# MotorControllerV7_HBridge2.net
KiCad netlist of a schematic drawn in EAGLE
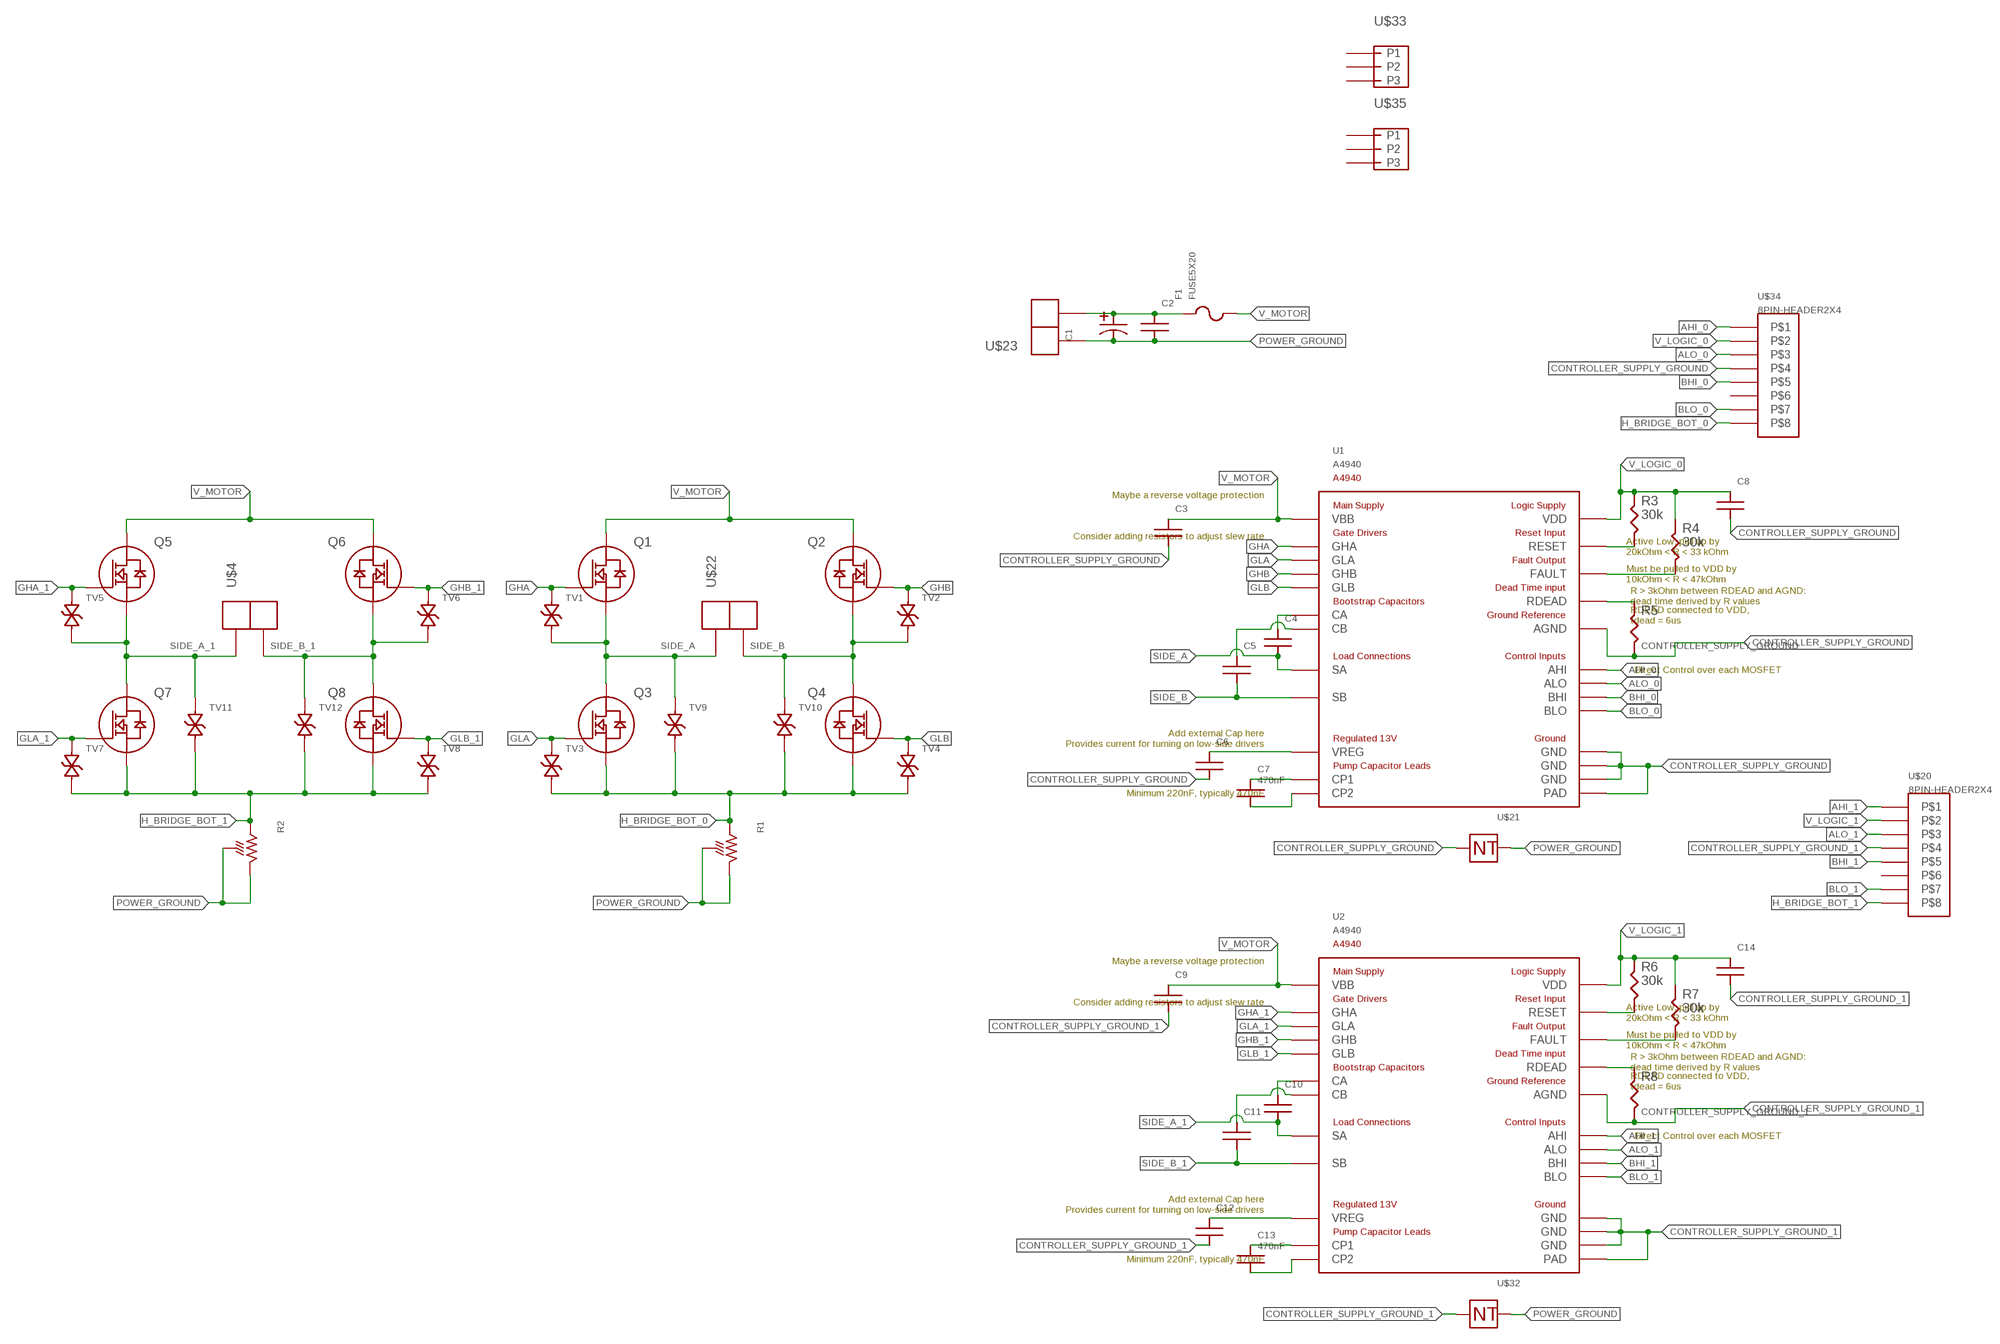
[diagram p0: schematic, sheet 1]

(export (version "E")
  (design (tool "Eeschema 10.0.6"))
  (components
    (comp (ref "C1")
      (value "CAPACITORESK_H4")
      (footprint "eagle-import:ESK_H4_CAPACITOR")
      (libsource (lib "eagle-import") (part "CAPACITORESK_H4"))
    )
    (comp (ref "C2")
      (value "CAPACITOR-UNPOLARIZED0805")
      (footprint "eagle-import:0805_STACKPOLERESISTOR")
      (libsource (lib "eagle-import") (part "CAPACITOR-UNPOLARIZED0805"))
    )
    (comp (ref "C3")
      (value "CAPACITOR-UNPOLARIZED0805")
      (footprint "eagle-import:0805_STACKPOLERESISTOR")
      (libsource (lib "eagle-import") (part "CAPACITOR-UNPOLARIZED0805"))
    )
    (comp (ref "C4")
      (value "CAPACITOR-UNPOLARIZED0805")
      (footprint "eagle-import:0805_STACKPOLERESISTOR")
      (libsource (lib "eagle-import") (part "CAPACITOR-UNPOLARIZED0805"))
    )
    (comp (ref "C5")
      (value "CAPACITOR-UNPOLARIZED0805")
      (footprint "eagle-import:0805_STACKPOLERESISTOR")
      (libsource (lib "eagle-import") (part "CAPACITOR-UNPOLARIZED0805"))
    )
    (comp (ref "C6")
      (value "CAPACITOR-UNPOLARIZED0805")
      (footprint "eagle-import:0805_STACKPOLERESISTOR")
      (libsource (lib "eagle-import") (part "CAPACITOR-UNPOLARIZED0805"))
    )
    (comp (ref "C7")
      (value "470nF")
      (footprint "eagle-import:0805_STACKPOLERESISTOR")
      (libsource (lib "eagle-import") (part "CAPACITOR-UNPOLARIZED0805"))
    )
    (comp (ref "C8")
      (value "CAPACITOR-UNPOLARIZED0805")
      (footprint "eagle-import:0805_STACKPOLERESISTOR")
      (libsource (lib "eagle-import") (part "CAPACITOR-UNPOLARIZED0805"))
    )
    (comp (ref "C9")
      (value "CAPACITOR-UNPOLARIZED0805")
      (footprint "eagle-import:0805_STACKPOLERESISTOR")
      (libsource (lib "eagle-import") (part "CAPACITOR-UNPOLARIZED0805"))
    )
    (comp (ref "C10")
      (value "CAPACITOR-UNPOLARIZED0805")
      (footprint "eagle-import:0805_STACKPOLERESISTOR")
      (libsource (lib "eagle-import") (part "CAPACITOR-UNPOLARIZED0805"))
    )
    (comp (ref "C11")
      (value "CAPACITOR-UNPOLARIZED0805")
      (footprint "eagle-import:0805_STACKPOLERESISTOR")
      (libsource (lib "eagle-import") (part "CAPACITOR-UNPOLARIZED0805"))
    )
    (comp (ref "C12")
      (value "CAPACITOR-UNPOLARIZED0805")
      (footprint "eagle-import:0805_STACKPOLERESISTOR")
      (libsource (lib "eagle-import") (part "CAPACITOR-UNPOLARIZED0805"))
    )
    (comp (ref "C13")
      (value "470nF")
      (footprint "eagle-import:0805_STACKPOLERESISTOR")
      (libsource (lib "eagle-import") (part "CAPACITOR-UNPOLARIZED0805"))
    )
    (comp (ref "C14")
      (value "CAPACITOR-UNPOLARIZED0805")
      (footprint "eagle-import:0805_STACKPOLERESISTOR")
      (libsource (lib "eagle-import") (part "CAPACITOR-UNPOLARIZED0805"))
    )
    (comp (ref "F1")
      (value "FUSE5X20")
      (footprint "eagle-import:LITTLEFUSE_5X20_HOLDER")
      (libsource (lib "eagle-import") (part "FUSE5X20"))
    )
    (comp (ref "Q1")
      (value "NMOSSOT669")
      (footprint "eagle-import:SOT669")
      (libsource (lib "eagle-import") (part "NMOSSOT669"))
    )
    (comp (ref "Q2")
      (value "NMOSSOT669")
      (footprint "eagle-import:SOT669")
      (libsource (lib "eagle-import") (part "NMOSSOT669"))
    )
    (comp (ref "Q3")
      (value "NMOSSOT669")
      (footprint "eagle-import:SOT669")
      (libsource (lib "eagle-import") (part "NMOSSOT669"))
    )
    (comp (ref "Q4")
      (value "NMOSSOT669")
      (footprint "eagle-import:SOT669")
      (libsource (lib "eagle-import") (part "NMOSSOT669"))
    )
    (comp (ref "Q5")
      (value "NMOSSOT669")
      (footprint "eagle-import:SOT669")
      (libsource (lib "eagle-import") (part "NMOSSOT669"))
    )
    (comp (ref "Q6")
      (value "NMOSSOT669")
      (footprint "eagle-import:SOT669")
      (libsource (lib "eagle-import") (part "NMOSSOT669"))
    )
    (comp (ref "Q7")
      (value "NMOSSOT669")
      (footprint "eagle-import:SOT669")
      (libsource (lib "eagle-import") (part "NMOSSOT669"))
    )
    (comp (ref "Q8")
      (value "NMOSSOT669")
      (footprint "eagle-import:SOT669")
      (libsource (lib "eagle-import") (part "NMOSSOT669"))
    )
    (comp (ref "R1")
      (value "RESISTOR_HEATSUNK")
      (footprint "eagle-import:TO-252")
      (libsource (lib "eagle-import") (part "RESISTOR_HEATSUNK"))
    )
    (comp (ref "R2")
      (value "RESISTOR_HEATSUNK")
      (footprint "eagle-import:TO-252")
      (libsource (lib "eagle-import") (part "RESISTOR_HEATSUNK"))
    )
    (comp (ref "R3")
      (value "30k")
      (footprint "eagle-import:0805_STACKPOLERESISTOR")
      (libsource (lib "eagle-import") (part "RESISTOR"))
    )
    (comp (ref "R4")
      (value "30k")
      (footprint "eagle-import:0805_STACKPOLERESISTOR")
      (libsource (lib "eagle-import") (part "RESISTOR"))
    )
    (comp (ref "R5")
      (value "RESISTOR")
      (footprint "eagle-import:0805_STACKPOLERESISTOR")
      (libsource (lib "eagle-import") (part "RESISTOR"))
    )
    (comp (ref "R6")
      (value "30k")
      (footprint "eagle-import:0805_STACKPOLERESISTOR")
      (libsource (lib "eagle-import") (part "RESISTOR"))
    )
    (comp (ref "R7")
      (value "30k")
      (footprint "eagle-import:0805_STACKPOLERESISTOR")
      (libsource (lib "eagle-import") (part "RESISTOR"))
    )
    (comp (ref "R8")
      (value "RESISTOR")
      (footprint "eagle-import:0805_STACKPOLERESISTOR")
      (libsource (lib "eagle-import") (part "RESISTOR"))
    )
    (comp (ref "TV1")
      (value "TVS_BIDIRECTIONALDO-214AC")
      (footprint "eagle-import:DO-214AC")
      (libsource (lib "eagle-import") (part "TVS_BIDIRECTIONALDO-214AC"))
    )
    (comp (ref "TV2")
      (value "TVS_BIDIRECTIONALDO-214AC")
      (footprint "eagle-import:DO-214AC")
      (libsource (lib "eagle-import") (part "TVS_BIDIRECTIONALDO-214AC"))
    )
    (comp (ref "TV3")
      (value "TVS_BIDIRECTIONALDO-214AC")
      (footprint "eagle-import:DO-214AC")
      (libsource (lib "eagle-import") (part "TVS_BIDIRECTIONALDO-214AC"))
    )
    (comp (ref "TV4")
      (value "TVS_BIDIRECTIONALDO-214AC")
      (footprint "eagle-import:DO-214AC")
      (libsource (lib "eagle-import") (part "TVS_BIDIRECTIONALDO-214AC"))
    )
    (comp (ref "TV5")
      (value "TVS_BIDIRECTIONALDO-214AC")
      (footprint "eagle-import:DO-214AC")
      (libsource (lib "eagle-import") (part "TVS_BIDIRECTIONALDO-214AC"))
    )
    (comp (ref "TV6")
      (value "TVS_BIDIRECTIONALDO-214AC")
      (footprint "eagle-import:DO-214AC")
      (libsource (lib "eagle-import") (part "TVS_BIDIRECTIONALDO-214AC"))
    )
    (comp (ref "TV7")
      (value "TVS_BIDIRECTIONALDO-214AC")
      (footprint "eagle-import:DO-214AC")
      (libsource (lib "eagle-import") (part "TVS_BIDIRECTIONALDO-214AC"))
    )
    (comp (ref "TV8")
      (value "TVS_BIDIRECTIONALDO-214AC")
      (footprint "eagle-import:DO-214AC")
      (libsource (lib "eagle-import") (part "TVS_BIDIRECTIONALDO-214AC"))
    )
    (comp (ref "TV9")
      (value "TVS_BIDIRECTIONAL")
      (footprint "eagle-import:SMB")
      (libsource (lib "eagle-import") (part "TVS_BIDIRECTIONAL"))
    )
    (comp (ref "TV10")
      (value "TVS_BIDIRECTIONAL")
      (footprint "eagle-import:SMB")
      (libsource (lib "eagle-import") (part "TVS_BIDIRECTIONAL"))
    )
    (comp (ref "TV11")
      (value "TVS_BIDIRECTIONAL")
      (footprint "eagle-import:SMB")
      (libsource (lib "eagle-import") (part "TVS_BIDIRECTIONAL"))
    )
    (comp (ref "TV12")
      (value "TVS_BIDIRECTIONAL")
      (footprint "eagle-import:SMB")
      (libsource (lib "eagle-import") (part "TVS_BIDIRECTIONAL"))
    )
    (comp (ref "U$4")
      (value "2PIN-HEADERANDERSON_RIGHTANGLE")
      (footprint "eagle-import:ANDERSON_RIGHTANGLE_X2")
      (libsource (lib "eagle-import") (part "2PIN-HEADERANDERSON_RIGHTANGLE"))
    )
    (comp (ref "U$20")
      (value "8PIN-HEADER2X4")
      (footprint "eagle-import:8PIN_2X4")
      (libsource (lib "eagle-import") (part "8PIN-HEADER2X4"))
    )
    (comp (ref "U$21")
      (value "NET_TIE1MM")
      (footprint "eagle-import:NET_TIE")
      (libsource (lib "eagle-import") (part "NET_TIE1MM"))
    )
    (comp (ref "U$22")
      (value "2PIN-HEADERANDERSON_RIGHTANGLE")
      (footprint "eagle-import:ANDERSON_RIGHTANGLE_X2")
      (libsource (lib "eagle-import") (part "2PIN-HEADERANDERSON_RIGHTANGLE"))
    )
    (comp (ref "U$23")
      (value "2PIN-HEADERANDERSON_RIGHTANGLE")
      (footprint "eagle-import:ANDERSON_RIGHTANGLE_X2")
      (libsource (lib "eagle-import") (part "2PIN-HEADERANDERSON_RIGHTANGLE"))
    )
    (comp (ref "U$32")
      (value "NET_TIE1MM")
      (footprint "eagle-import:NET_TIE")
      (libsource (lib "eagle-import") (part "NET_TIE1MM"))
    )
    (comp (ref "U$33")
      (value "3PIN_HEADER")
      (footprint "eagle-import:3PIN_HEADER")
      (libsource (lib "eagle-import") (part "3PIN_HEADER"))
    )
    (comp (ref "U$34")
      (value "8PIN-HEADER2X4")
      (footprint "eagle-import:8PIN_2X4")
      (libsource (lib "eagle-import") (part "8PIN-HEADER2X4"))
    )
    (comp (ref "U$35")
      (value "3PIN_HEADER")
      (footprint "eagle-import:3PIN_HEADER")
      (libsource (lib "eagle-import") (part "3PIN_HEADER"))
    )
    (comp (ref "U1")
      (value "A4940")
      (footprint "eagle-import:LP_24-PIN_TSSOP")
      (libsource (lib "eagle-import") (part "A4940"))
    )
    (comp (ref "U2")
      (value "A4940")
      (footprint "eagle-import:LP_24-PIN_TSSOP")
      (libsource (lib "eagle-import") (part "A4940"))
    )
  )
  (nets
    (net (code "1") (name "AHI_0") (class "Default")
      (node (ref "U$34") (pin "1") (pinfunction "P$1_1") (pintype "bidirectional"))
      (node (ref "U1") (pin "20") (pinfunction "AHI_20") (pintype "bidirectional"))
    )
    (net (code "2") (name "AHI_1") (class "Default")
      (node (ref "U$20") (pin "1") (pinfunction "P$1_1") (pintype "bidirectional"))
      (node (ref "U2") (pin "20") (pinfunction "AHI_20") (pintype "bidirectional"))
    )
    (net (code "3") (name "ALO_0") (class "Default")
      (node (ref "U$34") (pin "3") (pinfunction "P$3_3") (pintype "bidirectional"))
      (node (ref "U1") (pin "19") (pinfunction "ALO_19") (pintype "bidirectional"))
    )
    (net (code "4") (name "ALO_1") (class "Default")
      (node (ref "U$20") (pin "3") (pinfunction "P$3_3") (pintype "bidirectional"))
      (node (ref "U2") (pin "19") (pinfunction "ALO_19") (pintype "bidirectional"))
    )
    (net (code "5") (name "BHI_0") (class "Default")
      (node (ref "U$34") (pin "5") (pinfunction "P$5_5") (pintype "bidirectional"))
      (node (ref "U1") (pin "18") (pinfunction "BHI_18") (pintype "bidirectional"))
    )
    (net (code "6") (name "BHI_1") (class "Default")
      (node (ref "U$20") (pin "5") (pinfunction "P$5_5") (pintype "bidirectional"))
      (node (ref "U2") (pin "18") (pinfunction "BHI_18") (pintype "bidirectional"))
    )
    (net (code "7") (name "BLO_0") (class "Default")
      (node (ref "U$34") (pin "7") (pinfunction "P$7_7") (pintype "bidirectional"))
      (node (ref "U1") (pin "17") (pinfunction "BLO_17") (pintype "bidirectional"))
    )
    (net (code "8") (name "BLO_1") (class "Default")
      (node (ref "U$20") (pin "7") (pinfunction "P$7_7") (pintype "bidirectional"))
      (node (ref "U2") (pin "17") (pinfunction "BLO_17") (pintype "bidirectional"))
    )
    (net (code "9") (name "CONTROLLER_SUPPLY_GROUND") (class "Default")
      (node (ref "C3") (pin "P$2") (pinfunction "P$2_P$2") (pintype "bidirectional"))
      (node (ref "C6") (pin "P$2") (pinfunction "P$2_P$2") (pintype "bidirectional"))
      (node (ref "C8") (pin "P$2") (pinfunction "P$2_P$2") (pintype "bidirectional"))
      (node (ref "R5") (pin "P$2") (pinfunction "P$2_P$2") (pintype "bidirectional"))
      (node (ref "U$21") (pin "1") (pinfunction "P$1_1") (pintype "bidirectional"))
      (node (ref "U$34") (pin "4") (pinfunction "P$4_4") (pintype "bidirectional"))
      (node (ref "U1") (pin "15") (pinfunction "GND_15") (pintype "bidirectional"))
      (node (ref "U1") (pin "16") (pinfunction "GND_16") (pintype "bidirectional"))
      (node (ref "U1") (pin "2") (pinfunction "GND_2") (pintype "bidirectional"))
      (node (ref "U1") (pin "22") (pinfunction "AGND_22") (pintype "bidirectional"))
      (node (ref "U1") (pin "PAD") (pinfunction "PAD_PAD") (pintype "bidirectional"))
    )
    (net (code "10") (name "CONTROLLER_SUPPLY_GROUND_1") (class "Default")
      (node (ref "C12") (pin "P$2") (pinfunction "P$2_P$2") (pintype "bidirectional"))
      (node (ref "C14") (pin "P$2") (pinfunction "P$2_P$2") (pintype "bidirectional"))
      (node (ref "C9") (pin "P$2") (pinfunction "P$2_P$2") (pintype "bidirectional"))
      (node (ref "R8") (pin "P$2") (pinfunction "P$2_P$2") (pintype "bidirectional"))
      (node (ref "U$20") (pin "4") (pinfunction "P$4_4") (pintype "bidirectional"))
      (node (ref "U$32") (pin "1") (pinfunction "P$1_1") (pintype "bidirectional"))
      (node (ref "U2") (pin "15") (pinfunction "GND_15") (pintype "bidirectional"))
      (node (ref "U2") (pin "16") (pinfunction "GND_16") (pintype "bidirectional"))
      (node (ref "U2") (pin "2") (pinfunction "GND_2") (pintype "bidirectional"))
      (node (ref "U2") (pin "22") (pinfunction "AGND_22") (pintype "bidirectional"))
      (node (ref "U2") (pin "PAD") (pinfunction "PAD_PAD") (pintype "bidirectional"))
    )
    (net (code "11") (name "GHA") (class "Default")
      (node (ref "Q1") (pin "4") (pinfunction "GATE_4") (pintype "bidirectional"))
      (node (ref "TV1") (pin "P$2") (pinfunction "P$2_P$2") (pintype "bidirectional"))
      (node (ref "U1") (pin "9") (pinfunction "GHA_9") (pintype "bidirectional"))
    )
    (net (code "12") (name "GHA_1") (class "Default")
      (node (ref "Q5") (pin "4") (pinfunction "GATE_4") (pintype "bidirectional"))
      (node (ref "TV5") (pin "P$2") (pinfunction "P$2_P$2") (pintype "bidirectional"))
      (node (ref "U2") (pin "9") (pinfunction "GHA_9") (pintype "bidirectional"))
    )
    (net (code "13") (name "GHB") (class "Default")
      (node (ref "Q2") (pin "4") (pinfunction "GATE_4") (pintype "bidirectional"))
      (node (ref "TV2") (pin "P$2") (pinfunction "P$2_P$2") (pintype "bidirectional"))
      (node (ref "U1") (pin "5") (pinfunction "GHB_5") (pintype "bidirectional"))
    )
    (net (code "14") (name "GHB_1") (class "Default")
      (node (ref "Q6") (pin "4") (pinfunction "GATE_4") (pintype "bidirectional"))
      (node (ref "TV6") (pin "P$2") (pinfunction "P$2_P$2") (pintype "bidirectional"))
      (node (ref "U2") (pin "5") (pinfunction "GHB_5") (pintype "bidirectional"))
    )
    (net (code "15") (name "GLA") (class "Default")
      (node (ref "Q3") (pin "4") (pinfunction "GATE_4") (pintype "bidirectional"))
      (node (ref "TV3") (pin "P$2") (pinfunction "P$2_P$2") (pintype "bidirectional"))
      (node (ref "U1") (pin "11") (pinfunction "GLA_11") (pintype "bidirectional"))
    )
    (net (code "16") (name "GLA_1") (class "Default")
      (node (ref "Q7") (pin "4") (pinfunction "GATE_4") (pintype "bidirectional"))
      (node (ref "TV7") (pin "P$2") (pinfunction "P$2_P$2") (pintype "bidirectional"))
      (node (ref "U2") (pin "11") (pinfunction "GLA_11") (pintype "bidirectional"))
    )
    (net (code "17") (name "GLB") (class "Default")
      (node (ref "Q4") (pin "4") (pinfunction "GATE_4") (pintype "bidirectional"))
      (node (ref "TV4") (pin "P$2") (pinfunction "P$2_P$2") (pintype "bidirectional"))
      (node (ref "U1") (pin "3") (pinfunction "GLB_3") (pintype "bidirectional"))
    )
    (net (code "18") (name "GLB_1") (class "Default")
      (node (ref "Q8") (pin "4") (pinfunction "GATE_4") (pintype "bidirectional"))
      (node (ref "TV8") (pin "P$2") (pinfunction "P$2_P$2") (pintype "bidirectional"))
      (node (ref "U2") (pin "3") (pinfunction "GLB_3") (pintype "bidirectional"))
    )
    (net (code "19") (name "H_BRIDGE_BOT_0") (class "Default")
      (node (ref "Q3") (pin "1") (pinfunction "SOURCE_1") (pintype "bidirectional"))
      (node (ref "Q3") (pin "2") (pinfunction "SOURCE_2") (pintype "bidirectional"))
      (node (ref "Q3") (pin "3") (pinfunction "SOURCE_3") (pintype "bidirectional"))
      (node (ref "Q4") (pin "1") (pinfunction "SOURCE_1") (pintype "bidirectional"))
      (node (ref "Q4") (pin "2") (pinfunction "SOURCE_2") (pintype "bidirectional"))
      (node (ref "Q4") (pin "3") (pinfunction "SOURCE_3") (pintype "bidirectional"))
      (node (ref "R1") (pin "1") (pinfunction "1_1") (pintype "bidirectional"))
      (node (ref "TV10") (pin "1") (pinfunction "P$1_1") (pintype "bidirectional"))
      (node (ref "TV3") (pin "P$1") (pinfunction "P$1_P$1") (pintype "bidirectional"))
      (node (ref "TV4") (pin "P$1") (pinfunction "P$1_P$1") (pintype "bidirectional"))
      (node (ref "TV9") (pin "1") (pinfunction "P$1_1") (pintype "bidirectional"))
      (node (ref "U$34") (pin "8") (pinfunction "P$8_8") (pintype "bidirectional"))
    )
    (net (code "20") (name "H_BRIDGE_BOT_1") (class "Default")
      (node (ref "Q7") (pin "1") (pinfunction "SOURCE_1") (pintype "bidirectional"))
      (node (ref "Q7") (pin "2") (pinfunction "SOURCE_2") (pintype "bidirectional"))
      (node (ref "Q7") (pin "3") (pinfunction "SOURCE_3") (pintype "bidirectional"))
      (node (ref "Q8") (pin "1") (pinfunction "SOURCE_1") (pintype "bidirectional"))
      (node (ref "Q8") (pin "2") (pinfunction "SOURCE_2") (pintype "bidirectional"))
      (node (ref "Q8") (pin "3") (pinfunction "SOURCE_3") (pintype "bidirectional"))
      (node (ref "R2") (pin "1") (pinfunction "1_1") (pintype "bidirectional"))
      (node (ref "TV11") (pin "1") (pinfunction "P$1_1") (pintype "bidirectional"))
      (node (ref "TV12") (pin "1") (pinfunction "P$1_1") (pintype "bidirectional"))
      (node (ref "TV7") (pin "P$1") (pinfunction "P$1_P$1") (pintype "bidirectional"))
      (node (ref "TV8") (pin "P$1") (pinfunction "P$1_P$1") (pintype "bidirectional"))
      (node (ref "U$20") (pin "8") (pinfunction "P$8_8") (pintype "bidirectional"))
    )
    (net (code "21") (name "Net-(C1-POSITIVE_LEAD)") (class "Default")
      (node (ref "C1") (pin "POSITIVE_PAD") (pinfunction "POSITIVE_LEAD_POSITIVE_PAD") (pintype "bidirectional"))
      (node (ref "C2") (pin "P$1") (pinfunction "P$1_P$1") (pintype "bidirectional"))
      (node (ref "F1") (pin "LEFT_1") (pinfunction "P$1_LEFT_1") (pintype "bidirectional"))
      (node (ref "F1") (pin "LEFT_2") (pinfunction "P$1_LEFT_2") (pintype "bidirectional"))
      (node (ref "U$23") (pin "P2") (pinfunction "P$2_P2") (pintype "bidirectional"))
    )
    (net (code "22") (name "Net-(U1-CA)") (class "Default")
      (node (ref "C4") (pin "P$1") (pinfunction "P$1_P$1") (pintype "bidirectional"))
      (node (ref "U1") (pin "8") (pinfunction "CA_8") (pintype "bidirectional"))
    )
    (net (code "23") (name "Net-(U1-CB)") (class "Default")
      (node (ref "C5") (pin "P$1") (pinfunction "P$1_P$1") (pintype "bidirectional"))
      (node (ref "U1") (pin "6") (pinfunction "CB_6") (pintype "bidirectional"))
    )
    (net (code "24") (name "Net-(U1-CP1)") (class "Default")
      (node (ref "C7") (pin "P$1") (pinfunction "P$1_P$1") (pintype "bidirectional"))
      (node (ref "U1") (pin "14") (pinfunction "CP1_14") (pintype "bidirectional"))
    )
    (net (code "25") (name "Net-(U1-CP2)") (class "Default")
      (node (ref "C7") (pin "P$2") (pinfunction "P$2_P$2") (pintype "bidirectional"))
      (node (ref "U1") (pin "13") (pinfunction "CP2_13") (pintype "bidirectional"))
    )
    (net (code "26") (name "Net-(U1-FAULT)") (class "Default")
      (node (ref "R4") (pin "P$2") (pinfunction "P$2_P$2") (pintype "bidirectional"))
      (node (ref "U1") (pin "24") (pinfunction "FAULT_24") (pintype "bidirectional"))
    )
    (net (code "27") (name "Net-(U1-RDEAD)") (class "Default")
      (node (ref "R5") (pin "P$1") (pinfunction "P$1_P$1") (pintype "bidirectional"))
      (node (ref "U1") (pin "23") (pinfunction "RDEAD_23") (pintype "bidirectional"))
    )
    (net (code "28") (name "Net-(U1-RESET)") (class "Default")
      (node (ref "R3") (pin "P$2") (pinfunction "P$2_P$2") (pintype "bidirectional"))
      (node (ref "U1") (pin "1") (pinfunction "RESET_1") (pintype "bidirectional"))
    )
    (net (code "29") (name "Net-(U1-VREG)") (class "Default")
      (node (ref "C6") (pin "P$1") (pinfunction "P$1_P$1") (pintype "bidirectional"))
      (node (ref "U1") (pin "7") (pinfunction "VREG_7") (pintype "bidirectional"))
    )
    (net (code "30") (name "Net-(U2-CA)") (class "Default")
      (node (ref "C10") (pin "P$1") (pinfunction "P$1_P$1") (pintype "bidirectional"))
      (node (ref "U2") (pin "8") (pinfunction "CA_8") (pintype "bidirectional"))
    )
    (net (code "31") (name "Net-(U2-CB)") (class "Default")
      (node (ref "C11") (pin "P$1") (pinfunction "P$1_P$1") (pintype "bidirectional"))
      (node (ref "U2") (pin "6") (pinfunction "CB_6") (pintype "bidirectional"))
    )
    (net (code "32") (name "Net-(U2-CP1)") (class "Default")
      (node (ref "C13") (pin "P$1") (pinfunction "P$1_P$1") (pintype "bidirectional"))
      (node (ref "U2") (pin "14") (pinfunction "CP1_14") (pintype "bidirectional"))
    )
    (net (code "33") (name "Net-(U2-CP2)") (class "Default")
      (node (ref "C13") (pin "P$2") (pinfunction "P$2_P$2") (pintype "bidirectional"))
      (node (ref "U2") (pin "13") (pinfunction "CP2_13") (pintype "bidirectional"))
    )
    (net (code "34") (name "Net-(U2-FAULT)") (class "Default")
      (node (ref "R7") (pin "P$2") (pinfunction "P$2_P$2") (pintype "bidirectional"))
      (node (ref "U2") (pin "24") (pinfunction "FAULT_24") (pintype "bidirectional"))
    )
    (net (code "35") (name "Net-(U2-RDEAD)") (class "Default")
      (node (ref "R8") (pin "P$1") (pinfunction "P$1_P$1") (pintype "bidirectional"))
      (node (ref "U2") (pin "23") (pinfunction "RDEAD_23") (pintype "bidirectional"))
    )
    (net (code "36") (name "Net-(U2-RESET)") (class "Default")
      (node (ref "R6") (pin "P$2") (pinfunction "P$2_P$2") (pintype "bidirectional"))
      (node (ref "U2") (pin "1") (pinfunction "RESET_1") (pintype "bidirectional"))
    )
    (net (code "37") (name "Net-(U2-VREG)") (class "Default")
      (node (ref "C12") (pin "P$1") (pinfunction "P$1_P$1") (pintype "bidirectional"))
      (node (ref "U2") (pin "7") (pinfunction "VREG_7") (pintype "bidirectional"))
    )
    (net (code "38") (name "POWER_GROUND") (class "Default")
      (node (ref "C1") (pin "NEGATIVE_PAD") (pinfunction "NEGATIVE_LEAD_NEGATIVE_PAD") (pintype "bidirectional"))
      (node (ref "C2") (pin "P$2") (pinfunction "P$2_P$2") (pintype "bidirectional"))
      (node (ref "R1") (pin "2") (pinfunction "2_2") (pintype "bidirectional"))
      (node (ref "R1") (pin "TAB") (pinfunction "SINK_TAB") (pintype "bidirectional"))
      (node (ref "R2") (pin "2") (pinfunction "2_2") (pintype "bidirectional"))
      (node (ref "R2") (pin "TAB") (pinfunction "SINK_TAB") (pintype "bidirectional"))
      (node (ref "U$21") (pin "2") (pinfunction "P$2_2") (pintype "bidirectional"))
      (node (ref "U$23") (pin "P1") (pinfunction "P$1_P1") (pintype "bidirectional"))
      (node (ref "U$32") (pin "2") (pinfunction "P$2_2") (pintype "bidirectional"))
    )
    (net (code "39") (name "SIDE_A") (class "Default")
      (node (ref "C4") (pin "P$2") (pinfunction "P$2_P$2") (pintype "bidirectional"))
      (node (ref "Q1") (pin "1") (pinfunction "SOURCE_1") (pintype "bidirectional"))
      (node (ref "Q1") (pin "2") (pinfunction "SOURCE_2") (pintype "bidirectional"))
      (node (ref "Q1") (pin "3") (pinfunction "SOURCE_3") (pintype "bidirectional"))
      (node (ref "Q3") (pin "MB") (pinfunction "DRAIN_MB") (pintype "bidirectional"))
      (node (ref "TV1") (pin "P$1") (pinfunction "P$1_P$1") (pintype "bidirectional"))
      (node (ref "TV9") (pin "2") (pinfunction "P$2_2") (pintype "bidirectional"))
      (node (ref "U$22") (pin "P1") (pinfunction "P$1_P1") (pintype "bidirectional"))
      (node (ref "U1") (pin "10") (pinfunction "SA_10") (pintype "bidirectional"))
    )
    (net (code "40") (name "SIDE_A_1") (class "Default")
      (node (ref "C10") (pin "P$2") (pinfunction "P$2_P$2") (pintype "bidirectional"))
      (node (ref "Q5") (pin "1") (pinfunction "SOURCE_1") (pintype "bidirectional"))
      (node (ref "Q5") (pin "2") (pinfunction "SOURCE_2") (pintype "bidirectional"))
      (node (ref "Q5") (pin "3") (pinfunction "SOURCE_3") (pintype "bidirectional"))
      (node (ref "Q7") (pin "MB") (pinfunction "DRAIN_MB") (pintype "bidirectional"))
      (node (ref "TV11") (pin "2") (pinfunction "P$2_2") (pintype "bidirectional"))
      (node (ref "TV5") (pin "P$1") (pinfunction "P$1_P$1") (pintype "bidirectional"))
      (node (ref "U$4") (pin "P1") (pinfunction "P$1_P1") (pintype "bidirectional"))
      (node (ref "U2") (pin "10") (pinfunction "SA_10") (pintype "bidirectional"))
    )
    (net (code "41") (name "SIDE_B") (class "Default")
      (node (ref "C5") (pin "P$2") (pinfunction "P$2_P$2") (pintype "bidirectional"))
      (node (ref "Q2") (pin "1") (pinfunction "SOURCE_1") (pintype "bidirectional"))
      (node (ref "Q2") (pin "2") (pinfunction "SOURCE_2") (pintype "bidirectional"))
      (node (ref "Q2") (pin "3") (pinfunction "SOURCE_3") (pintype "bidirectional"))
      (node (ref "Q4") (pin "MB") (pinfunction "DRAIN_MB") (pintype "bidirectional"))
      (node (ref "TV10") (pin "2") (pinfunction "P$2_2") (pintype "bidirectional"))
      (node (ref "TV2") (pin "P$1") (pinfunction "P$1_P$1") (pintype "bidirectional"))
      (node (ref "U$22") (pin "P2") (pinfunction "P$2_P2") (pintype "bidirectional"))
      (node (ref "U1") (pin "4") (pinfunction "SB_4") (pintype "bidirectional"))
    )
    (net (code "42") (name "SIDE_B_1") (class "Default")
      (node (ref "C11") (pin "P$2") (pinfunction "P$2_P$2") (pintype "bidirectional"))
      (node (ref "Q6") (pin "1") (pinfunction "SOURCE_1") (pintype "bidirectional"))
      (node (ref "Q6") (pin "2") (pinfunction "SOURCE_2") (pintype "bidirectional"))
      (node (ref "Q6") (pin "3") (pinfunction "SOURCE_3") (pintype "bidirectional"))
      (node (ref "Q8") (pin "MB") (pinfunction "DRAIN_MB") (pintype "bidirectional"))
      (node (ref "TV12") (pin "2") (pinfunction "P$2_2") (pintype "bidirectional"))
      (node (ref "TV6") (pin "P$1") (pinfunction "P$1_P$1") (pintype "bidirectional"))
      (node (ref "U$4") (pin "P2") (pinfunction "P$2_P2") (pintype "bidirectional"))
      (node (ref "U2") (pin "4") (pinfunction "SB_4") (pintype "bidirectional"))
    )
    (net (code "43") (name "V_LOGIC_0") (class "Default")
      (node (ref "C8") (pin "P$1") (pinfunction "P$1_P$1") (pintype "bidirectional"))
      (node (ref "R3") (pin "P$1") (pinfunction "P$1_P$1") (pintype "bidirectional"))
      (node (ref "R4") (pin "P$1") (pinfunction "P$1_P$1") (pintype "bidirectional"))
      (node (ref "U$34") (pin "2") (pinfunction "P$2_2") (pintype "bidirectional"))
      (node (ref "U1") (pin "21") (pinfunction "VDD_21") (pintype "bidirectional"))
    )
    (net (code "44") (name "V_LOGIC_1") (class "Default")
      (node (ref "C14") (pin "P$1") (pinfunction "P$1_P$1") (pintype "bidirectional"))
      (node (ref "R6") (pin "P$1") (pinfunction "P$1_P$1") (pintype "bidirectional"))
      (node (ref "R7") (pin "P$1") (pinfunction "P$1_P$1") (pintype "bidirectional"))
      (node (ref "U$20") (pin "2") (pinfunction "P$2_2") (pintype "bidirectional"))
      (node (ref "U2") (pin "21") (pinfunction "VDD_21") (pintype "bidirectional"))
    )
    (net (code "45") (name "V_MOTOR") (class "Default")
      (node (ref "C3") (pin "P$1") (pinfunction "P$1_P$1") (pintype "bidirectional"))
      (node (ref "C9") (pin "P$1") (pinfunction "P$1_P$1") (pintype "bidirectional"))
      (node (ref "F1") (pin "RIGHT_1") (pinfunction "P$2_RIGHT_1") (pintype "bidirectional"))
      (node (ref "F1") (pin "RIGHT_2") (pinfunction "P$2_RIGHT_2") (pintype "bidirectional"))
      (node (ref "Q1") (pin "MB") (pinfunction "DRAIN_MB") (pintype "bidirectional"))
      (node (ref "Q2") (pin "MB") (pinfunction "DRAIN_MB") (pintype "bidirectional"))
      (node (ref "Q5") (pin "MB") (pinfunction "DRAIN_MB") (pintype "bidirectional"))
      (node (ref "Q6") (pin "MB") (pinfunction "DRAIN_MB") (pintype "bidirectional"))
      (node (ref "U1") (pin "12") (pinfunction "VBB_12") (pintype "bidirectional"))
      (node (ref "U2") (pin "12") (pinfunction "VBB_12") (pintype "bidirectional"))
    )
    (net (code "46") (name "unconnected-(U$20-P$6-Pad6)") (class "Default")
      (node (ref "U$20") (pin "6") (pinfunction "P$6_6") (pintype "bidirectional"))
    )
    (net (code "47") (name "unconnected-(U$33-PadP1)") (class "Default")
      (node (ref "U$33") (pin "P1") (pinfunction "P1_P1") (pintype "bidirectional"))
    )
    (net (code "48") (name "unconnected-(U$33-PadP2)") (class "Default")
      (node (ref "U$33") (pin "P2") (pinfunction "P2_P2") (pintype "bidirectional"))
    )
    (net (code "49") (name "unconnected-(U$33-PadP3)") (class "Default")
      (node (ref "U$33") (pin "P3") (pinfunction "P3_P3") (pintype "bidirectional"))
    )
    (net (code "50") (name "unconnected-(U$34-P$6-Pad6)") (class "Default")
      (node (ref "U$34") (pin "6") (pinfunction "P$6_6") (pintype "bidirectional"))
    )
    (net (code "51") (name "unconnected-(U$35-PadP1)") (class "Default")
      (node (ref "U$35") (pin "P1") (pinfunction "P1_P1") (pintype "bidirectional"))
    )
    (net (code "52") (name "unconnected-(U$35-PadP2)") (class "Default")
      (node (ref "U$35") (pin "P2") (pinfunction "P2_P2") (pintype "bidirectional"))
    )
    (net (code "53") (name "unconnected-(U$35-PadP3)") (class "Default")
      (node (ref "U$35") (pin "P3") (pinfunction "P3_P3") (pintype "bidirectional"))
    )
  )
)
